# Sheet1.net
KiCad netlist of a schematic drawn in Altium Designer
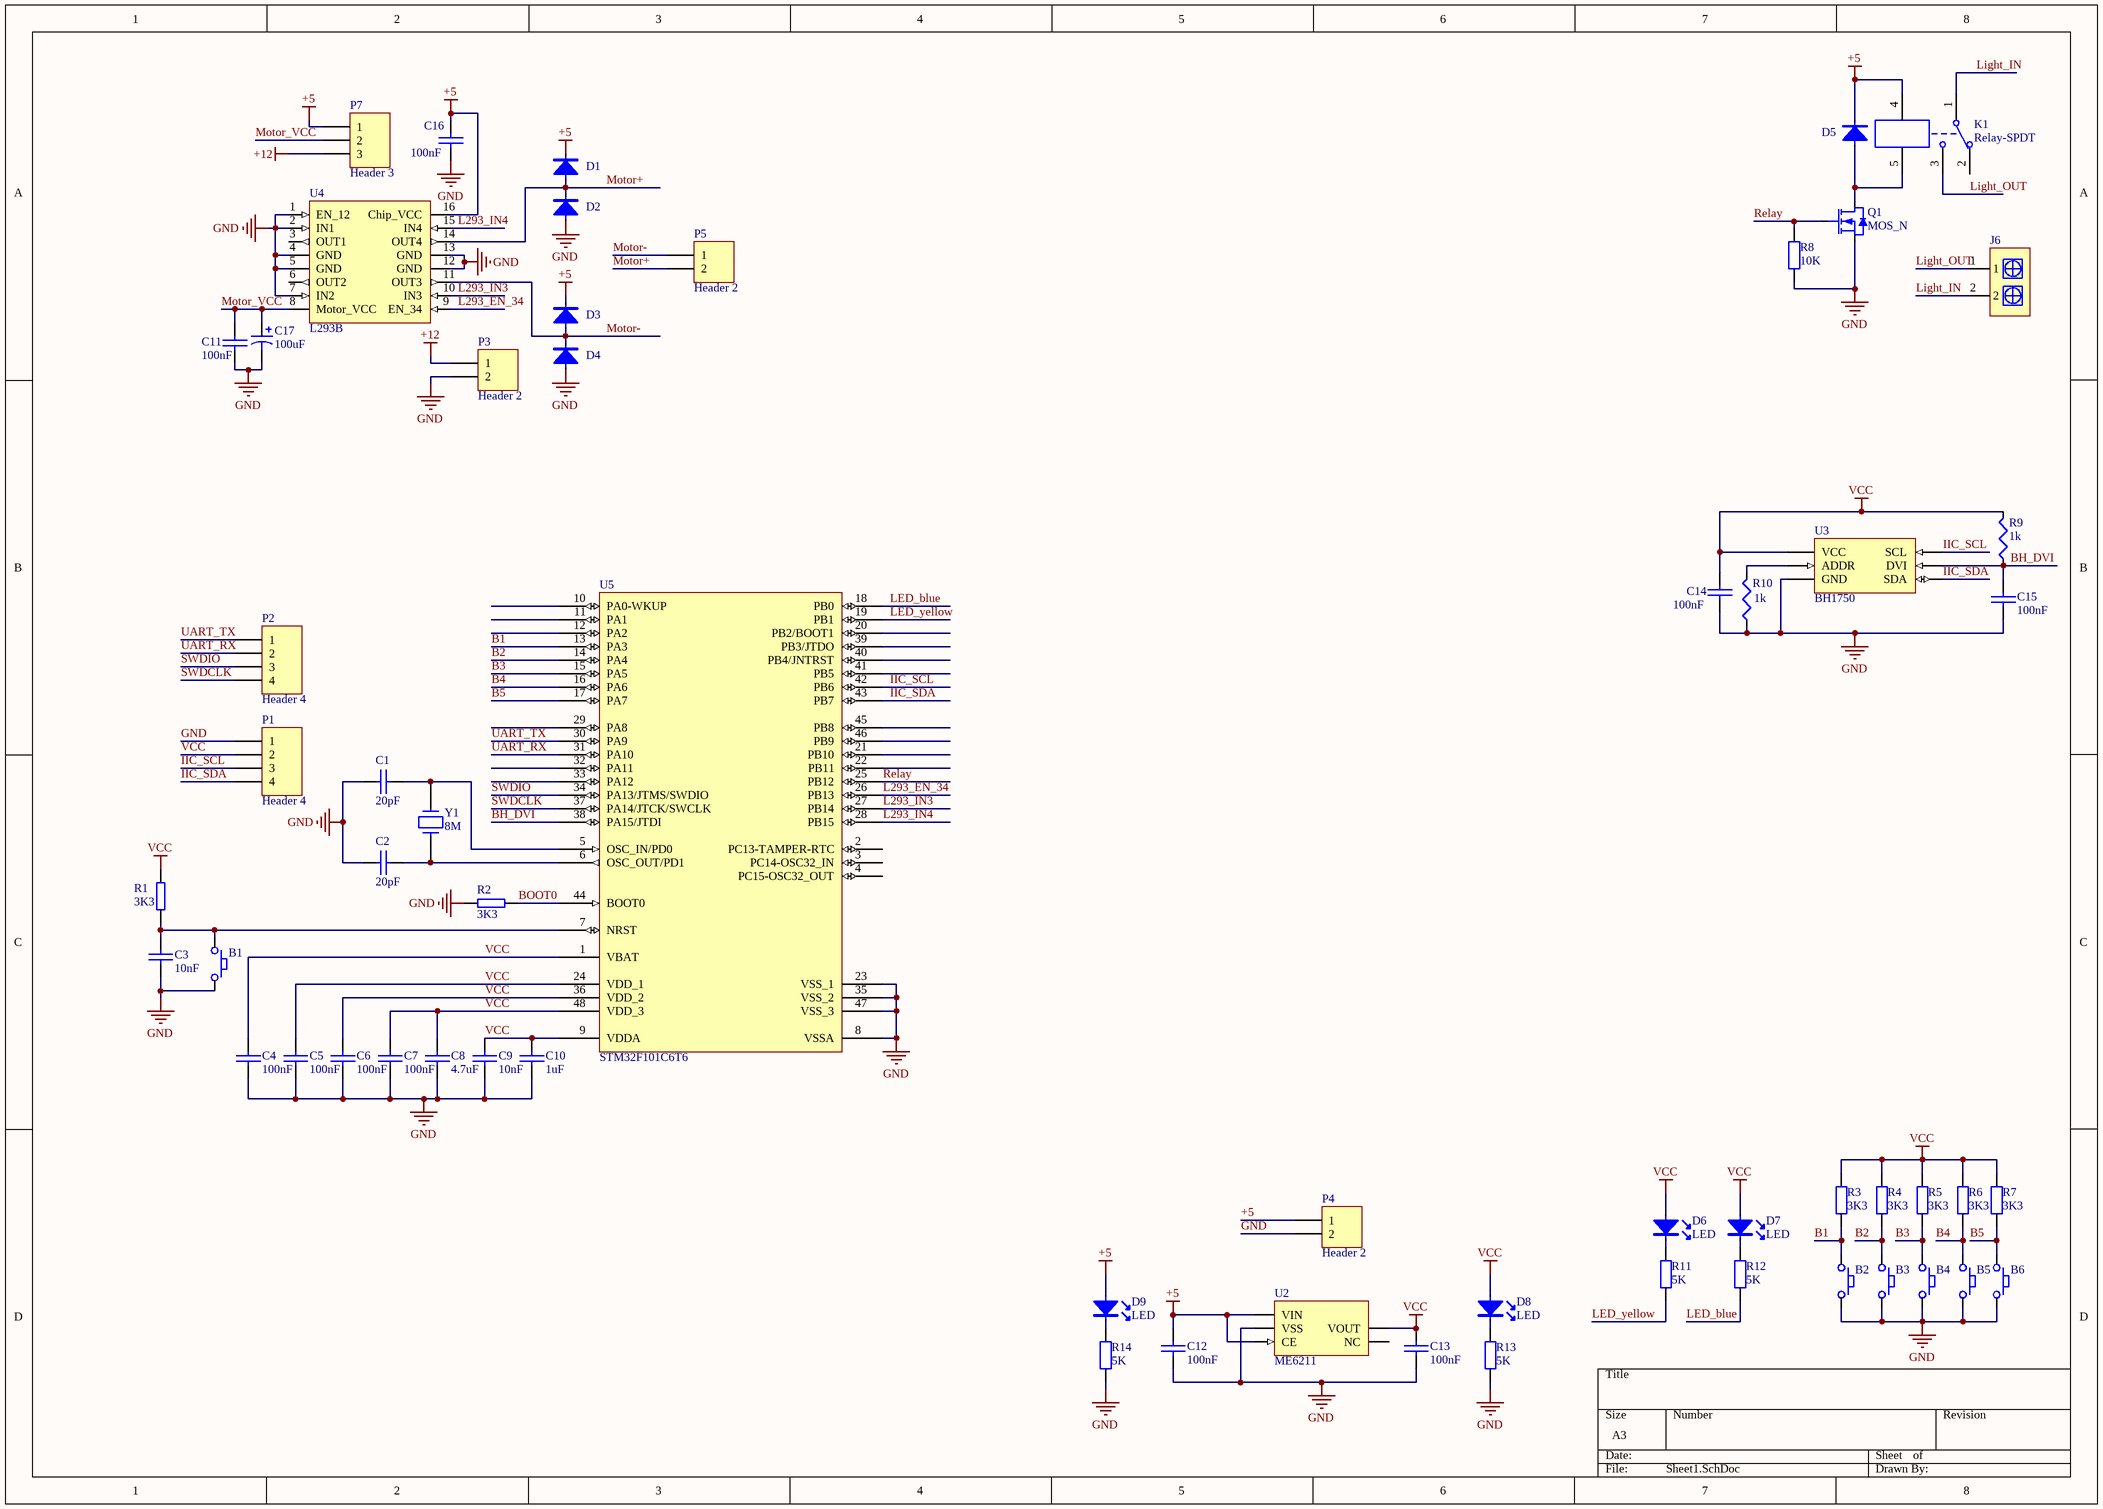
[diagram p0: Sheet1.SchDoc]

(export (version "E")
  (design (tool "Eeschema 10.0.6"))
  (components
    (comp (ref "B1") (value "button") (footprint "switch_2P") (libsource (lib "mylib") (part "button")))
    (comp (ref "B2") (value "button") (footprint "switch_2P") (libsource (lib "mylib") (part "button")))
    (comp (ref "B3") (value "button") (footprint "switch_2P") (libsource (lib "mylib") (part "button")))
    (comp (ref "B4") (value "button") (footprint "switch_2P") (libsource (lib "mylib") (part "button")))
    (comp (ref "B5") (value "button") (footprint "switch_2P") (libsource (lib "mylib") (part "button")))
    (comp (ref "B6") (value "button") (footprint "switch_2P") (libsource (lib "mylib") (part "button")))
    (comp (ref "C1")
      (value "20pF")
      (footprint "0603")
      (description "电容")
      (libsource (lib "SCH") (part "CAP"))
    )
    (comp (ref "C2")
      (value "20pF")
      (footprint "0603")
      (description "电容")
      (libsource (lib "SCH") (part "CAP"))
    )
    (comp (ref "C3")
      (value "10nF")
      (footprint "0603")
      (description "电容")
      (libsource (lib "SCH") (part "CAP"))
    )
    (comp (ref "C4")
      (value "100nF")
      (footprint "0603")
      (description "电容")
      (libsource (lib "SCH") (part "CAP"))
    )
    (comp (ref "C5")
      (value "100nF")
      (footprint "0603")
      (description "电容")
      (libsource (lib "SCH") (part "CAP"))
    )
    (comp (ref "C6")
      (value "100nF")
      (footprint "0603")
      (description "电容")
      (libsource (lib "SCH") (part "CAP"))
    )
    (comp (ref "C7")
      (value "100nF")
      (footprint "0603")
      (description "电容")
      (libsource (lib "SCH") (part "CAP"))
    )
    (comp (ref "C8")
      (value "4.7uF")
      (footprint "0603")
      (description "电容")
      (libsource (lib "SCH") (part "CAP"))
    )
    (comp (ref "C9")
      (value "10nF")
      (footprint "0603")
      (description "电容")
      (libsource (lib "SCH") (part "CAP"))
    )
    (comp (ref "C10")
      (value "1uF")
      (footprint "0603")
      (description "电容")
      (libsource (lib "SCH") (part "CAP"))
    )
    (comp (ref "C11")
      (value "100nF")
      (footprint "0603")
      (description "电容")
      (libsource (lib "SCH") (part "CAP"))
    )
    (comp (ref "C12")
      (value "100nF")
      (footprint "0603")
      (description "电容")
      (libsource (lib "SCH") (part "CAP"))
    )
    (comp (ref "C13")
      (value "100nF")
      (footprint "0603")
      (description "电容")
      (libsource (lib "SCH") (part "CAP"))
    )
    (comp (ref "C14")
      (value "100nF")
      (footprint "0603")
      (description "电容")
      (libsource (lib "SCH") (part "CAP"))
    )
    (comp (ref "C15")
      (value "100nF")
      (footprint "0603")
      (description "电容")
      (libsource (lib "SCH") (part "CAP"))
    )
    (comp (ref "C16")
      (value "100nF")
      (footprint "0603")
      (description "电容")
      (libsource (lib "SCH") (part "CAP"))
    )
    (comp (ref "C17")
      (value "100uF")
      (footprint "CAP_3.5_8mm")
      (description "Polarized Capacitor (Radial)")
      (fields (field (name "PUBLISHER") "Altium Limited"))
      (libsource (lib "Miscellaneous Devices") (part "Cap Pol1"))
    )
    (comp (ref "D1")
      (value "Diode_short")
      (footprint "SOD_123")
      (libsource (lib "mylib") (part "Diode_short"))
    )
    (comp (ref "D2")
      (value "Diode_short")
      (footprint "SOD_123")
      (libsource (lib "mylib") (part "Diode_short"))
    )
    (comp (ref "D3")
      (value "Diode_short")
      (footprint "SOD_123")
      (libsource (lib "mylib") (part "Diode_short"))
    )
    (comp (ref "D4")
      (value "Diode_short")
      (footprint "SOD_123")
      (libsource (lib "mylib") (part "Diode_short"))
    )
    (comp (ref "D5")
      (value "Diode_short")
      (footprint "SOD_123")
      (libsource (lib "mylib") (part "Diode_short"))
    )
    (comp (ref "D6") (value "LED") (footprint "0603-led") (libsource (lib "mylib") (part "LED")))
    (comp (ref "D7") (value "LED") (footprint "0603-led") (libsource (lib "mylib") (part "LED")))
    (comp (ref "D8") (value "LED") (footprint "0603-led") (libsource (lib "mylib") (part "LED")))
    (comp (ref "D9") (value "LED") (footprint "0603-led") (libsource (lib "mylib") (part "LED")))
    (comp (ref "J6")
      (value "7.62_螺丝固定端子")
      (footprint "7.62螺丝端子座")
      (libsource (lib "mylib") (part "7.62_螺丝固定端子"))
    )
    (comp (ref "K1")
      (value "Relay-SPDT")
      (footprint "relay_5pin")
      (description "Single-Pole Dual-Throw Relay")
      (fields (field (name "PUBLISHER") "Altium Limited"))
      (libsource (lib "Miscellaneous Devices") (part "Relay-SPDT"))
    )
    (comp (ref "P1")
      (value "Header 4")
      (footprint "HDR1X4")
      (description "Header, 4-Pin")
      (fields (field (name "PUBLISHER") "Altium Limited"))
      (libsource (lib "Miscellaneous Connectors") (part "Header 4"))
    )
    (comp (ref "P2")
      (value "Header 4")
      (footprint "HDR1X4")
      (description "Header, 4-Pin")
      (fields (field (name "PUBLISHER") "Altium Limited"))
      (libsource (lib "Miscellaneous Connectors") (part "Header 4"))
    )
    (comp (ref "P3")
      (value "Header 2")
      (footprint "HDR1X2")
      (description "Header, 2-Pin")
      (fields (field (name "PUBLISHER") "Altium Limited"))
      (libsource (lib "Miscellaneous Connectors") (part "Header 2"))
    )
    (comp (ref "P4")
      (value "Header 2")
      (footprint "HDR1X2")
      (description "Header, 2-Pin")
      (fields (field (name "PUBLISHER") "Altium Limited"))
      (libsource (lib "Miscellaneous Connectors") (part "Header 2"))
    )
    (comp (ref "P5")
      (value "Header 2")
      (footprint "2P_螺钉式接线端子_5.08mm")
      (description "Header, 2-Pin")
      (fields (field (name "PUBLISHER") "Altium Limited"))
      (libsource (lib "Miscellaneous Connectors") (part "Header 2"))
    )
    (comp (ref "P7")
      (value "Header 3")
      (footprint "HDR1X3")
      (description "Header, 3-Pin")
      (fields (field (name "PUBLISHER") "Altium Limited"))
      (libsource (lib "Miscellaneous Connectors") (part "Header 3"))
    )
    (comp (ref "Q1") (value "MOS_N") (footprint "zhang_PCB:SOT-23") (libsource (lib "mylib") (part "MOS_N")))
    (comp (ref "R1") (value "3K3") (footprint "0603") (libsource (lib "SCH") (part "RES2")))
    (comp (ref "R2") (value "3K3") (footprint "0603") (libsource (lib "SCH") (part "RES2")))
    (comp (ref "R3")
      (value "3K3")
      (footprint "0603")
      (description "Resistor")
      (fields (field (name "PUBLISHER") "Altium Limited"))
      (libsource (lib "Miscellaneous Devices") (part "Res2"))
    )
    (comp (ref "R4")
      (value "3K3")
      (footprint "0603")
      (description "Resistor")
      (fields (field (name "PUBLISHER") "Altium Limited"))
      (libsource (lib "Miscellaneous Devices") (part "Res2"))
    )
    (comp (ref "R5")
      (value "3K3")
      (footprint "0603")
      (description "Resistor")
      (fields (field (name "PUBLISHER") "Altium Limited"))
      (libsource (lib "Miscellaneous Devices") (part "Res2"))
    )
    (comp (ref "R6")
      (value "3K3")
      (footprint "0603")
      (description "Resistor")
      (fields (field (name "PUBLISHER") "Altium Limited"))
      (libsource (lib "Miscellaneous Devices") (part "Res2"))
    )
    (comp (ref "R7")
      (value "3K3")
      (footprint "0603")
      (description "Resistor")
      (fields (field (name "PUBLISHER") "Altium Limited"))
      (libsource (lib "Miscellaneous Devices") (part "Res2"))
    )
    (comp (ref "R8")
      (value "10K")
      (footprint "0603")
      (description "Resistor")
      (fields (field (name "PUBLISHER") "Altium Limited"))
      (libsource (lib "Miscellaneous Devices") (part "Res2"))
    )
    (comp (ref "R9") (value "1k") (footprint "0603") (libsource (lib "zhang_SCH") (part "RES1")))
    (comp (ref "R10") (value "1k") (footprint "0603") (libsource (lib "zhang_SCH") (part "RES1")))
    (comp (ref "R11")
      (value "5K")
      (footprint "0603")
      (description "Resistor")
      (fields (field (name "PUBLISHER") "Altium Limited"))
      (libsource (lib "Miscellaneous Devices") (part "Res2"))
    )
    (comp (ref "R12")
      (value "5K")
      (footprint "0603")
      (description "Resistor")
      (fields (field (name "PUBLISHER") "Altium Limited"))
      (libsource (lib "Miscellaneous Devices") (part "Res2"))
    )
    (comp (ref "R13")
      (value "5K")
      (footprint "0603")
      (description "Resistor")
      (fields (field (name "PUBLISHER") "Altium Limited"))
      (libsource (lib "Miscellaneous Devices") (part "Res2"))
    )
    (comp (ref "R14")
      (value "5K")
      (footprint "0603")
      (description "Resistor")
      (fields (field (name "PUBLISHER") "Altium Limited"))
      (libsource (lib "Miscellaneous Devices") (part "Res2"))
    )
    (comp (ref "U2") (value "ME6211") (footprint "SOT-23-5") (libsource (lib "mylib") (part "ME6211")))
    (comp (ref "U3") (value "BH1750") (footprint "BH1750") (libsource (lib "mylib") (part "BH1750")))
    (comp (ref "U4")
      (value "L293B")
      (footprint "DIP16")
      (description "4路电机驱动器")
      (libsource (lib "mylib") (part "L293B"))
    )
    (comp (ref "U5")
      (value "STM32F101C6T6")
      (footprint "LQFP48_M")
      (description "STM32 ARM-based 32-bit MCU with 32 Kbytes Flash, 48-pin LQFP, Industrial Temperature")
      (fields (field (name "PUBLISHER") "Altium Limited"))
      (libsource (lib "ST Microcontroller 32-Bit STM32") (part "STM32F101C6T6"))
    )
    (comp (ref "Y1")
      (value "8M")
      (footprint "mylib:5032")
      (description "晶体谐振器")
      (libsource (lib "SCH") (part "CRYSTAL"))
    )
  )
  (nets
    (net (code "1") (name "+5") (class "Default")
      (node (ref "C12") (pin "2") (pinfunction "2_2") (pintype "passive"))
      (node (ref "C16") (pin "2") (pinfunction "2_2") (pintype "passive"))
      (node (ref "D1") (pin "2") (pinfunction "2_2") (pintype "passive"))
      (node (ref "D3") (pin "2") (pinfunction "2_2") (pintype "passive"))
      (node (ref "D5") (pin "2") (pinfunction "2_2") (pintype "passive"))
      (node (ref "D9") (pin "1") (pinfunction "1_1") (pintype "passive"))
      (node (ref "K1") (pin "4") (pinfunction "4_4") (pintype "passive"))
      (node (ref "P4") (pin "1") (pinfunction "1_1") (pintype "passive"))
      (node (ref "P7") (pin "1") (pinfunction "1_1") (pintype "passive"))
      (node (ref "U2") (pin "1") (pinfunction "VIN_1") (pintype "power_in"))
      (node (ref "U2") (pin "3") (pinfunction "CE_3") (pintype "input"))
      (node (ref "U4") (pin "16") (pinfunction "Chip_VCC_16") (pintype "power_in"))
    )
    (net (code "2") (name "+12") (class "Default")
      (node (ref "P3") (pin "1") (pinfunction "1_1") (pintype "passive"))
      (node (ref "P7") (pin "3") (pinfunction "3_3") (pintype "passive"))
    )
    (net (code "3") (name "/B1") (class "Default")
      (node (ref "B2") (pin "1") (pinfunction "1_1") (pintype "passive"))
      (node (ref "R3") (pin "2") (pinfunction "2_2") (pintype "passive"))
      (node (ref "U5") (pin "13") (pinfunction "PA3_13") (pintype "bidirectional"))
    )
    (net (code "4") (name "/B2") (class "Default")
      (node (ref "B3") (pin "1") (pinfunction "1_1") (pintype "passive"))
      (node (ref "R4") (pin "2") (pinfunction "2_2") (pintype "passive"))
      (node (ref "U5") (pin "14") (pinfunction "PA4_14") (pintype "bidirectional"))
    )
    (net (code "5") (name "/B3") (class "Default")
      (node (ref "B4") (pin "1") (pinfunction "1_1") (pintype "passive"))
      (node (ref "R5") (pin "2") (pinfunction "2_2") (pintype "passive"))
      (node (ref "U5") (pin "15") (pinfunction "PA5_15") (pintype "bidirectional"))
    )
    (net (code "6") (name "/B4") (class "Default")
      (node (ref "B5") (pin "1") (pinfunction "1_1") (pintype "passive"))
      (node (ref "R6") (pin "2") (pinfunction "2_2") (pintype "passive"))
      (node (ref "U5") (pin "16") (pinfunction "PA6_16") (pintype "bidirectional"))
    )
    (net (code "7") (name "/B5") (class "Default")
      (node (ref "B6") (pin "1") (pinfunction "1_1") (pintype "passive"))
      (node (ref "R7") (pin "2") (pinfunction "2_2") (pintype "passive"))
      (node (ref "U5") (pin "17") (pinfunction "PA7_17") (pintype "bidirectional"))
    )
    (net (code "8") (name "/BH_DVI") (class "Default")
      (node (ref "C15") (pin "2") (pinfunction "2_2") (pintype "passive"))
      (node (ref "R9") (pin "1") (pinfunction "1_1") (pintype "passive"))
      (node (ref "U3") (pin "5") (pinfunction "DVI_5") (pintype "input"))
      (node (ref "U5") (pin "38") (pinfunction "PA15/JTDI_38") (pintype "bidirectional"))
    )
    (net (code "9") (name "/BOOT0") (class "Default")
      (node (ref "R2") (pin "2") (pinfunction "2_2") (pintype "passive"))
      (node (ref "U5") (pin "44") (pinfunction "BOOT0_44") (pintype "input"))
    )
    (net (code "10") (name "/IIC_SCL") (class "Default")
      (node (ref "P1") (pin "3") (pinfunction "3_3") (pintype "passive"))
      (node (ref "U3") (pin "6") (pinfunction "SCL_6") (pintype "input"))
      (node (ref "U5") (pin "42") (pinfunction "PB6_42") (pintype "bidirectional"))
    )
    (net (code "11") (name "/IIC_SDA") (class "Default")
      (node (ref "P1") (pin "4") (pinfunction "4_4") (pintype "passive"))
      (node (ref "U3") (pin "4") (pinfunction "SDA_4") (pintype "bidirectional"))
      (node (ref "U5") (pin "43") (pinfunction "PB7_43") (pintype "bidirectional"))
    )
    (net (code "12") (name "/L293_EN_34") (class "Default")
      (node (ref "U4") (pin "9") (pinfunction "EN_34_9") (pintype "input"))
      (node (ref "U5") (pin "26") (pinfunction "PB13_26") (pintype "bidirectional"))
    )
    (net (code "13") (name "/L293_IN3") (class "Default")
      (node (ref "U4") (pin "10") (pinfunction "IN3_10") (pintype "input"))
      (node (ref "U5") (pin "27") (pinfunction "PB14_27") (pintype "bidirectional"))
    )
    (net (code "14") (name "/L293_IN4") (class "Default")
      (node (ref "U4") (pin "15") (pinfunction "IN4_15") (pintype "input"))
      (node (ref "U5") (pin "28") (pinfunction "PB15_28") (pintype "bidirectional"))
    )
    (net (code "15") (name "/LED_blue") (class "Default")
      (node (ref "R12") (pin "2") (pinfunction "2_2") (pintype "passive"))
      (node (ref "U5") (pin "18") (pinfunction "PB0_18") (pintype "bidirectional"))
    )
    (net (code "16") (name "/LED_yellow") (class "Default")
      (node (ref "R11") (pin "2") (pinfunction "2_2") (pintype "passive"))
      (node (ref "U5") (pin "19") (pinfunction "PB1_19") (pintype "bidirectional"))
    )
    (net (code "17") (name "/Light_IN") (class "Default")
      (node (ref "J6") (pin "2") (pinfunction "2_2") (pintype "passive"))
      (node (ref "K1") (pin "1") (pinfunction "1_1") (pintype "passive"))
    )
    (net (code "18") (name "/Light_OUT") (class "Default")
      (node (ref "J6") (pin "1") (pinfunction "1_1") (pintype "passive"))
      (node (ref "K1") (pin "3") (pinfunction "3_3") (pintype "passive"))
    )
    (net (code "19") (name "/Motor+") (class "Default")
      (node (ref "D1") (pin "1") (pinfunction "1_1") (pintype "passive"))
      (node (ref "D2") (pin "2") (pinfunction "2_2") (pintype "passive"))
      (node (ref "P5") (pin "2") (pinfunction "2_2") (pintype "passive"))
      (node (ref "U4") (pin "14") (pinfunction "OUT4_14") (pintype "output"))
    )
    (net (code "20") (name "/Motor-") (class "Default")
      (node (ref "D3") (pin "1") (pinfunction "1_1") (pintype "passive"))
      (node (ref "D4") (pin "2") (pinfunction "2_2") (pintype "passive"))
      (node (ref "P5") (pin "1") (pinfunction "1_1") (pintype "passive"))
      (node (ref "U4") (pin "11") (pinfunction "OUT3_11") (pintype "output"))
    )
    (net (code "21") (name "/Motor_VCC") (class "Default")
      (node (ref "C11") (pin "2") (pinfunction "2_2") (pintype "passive"))
      (node (ref "C17") (pin "1") (pinfunction "1_1") (pintype "passive"))
      (node (ref "P7") (pin "2") (pinfunction "2_2") (pintype "passive"))
      (node (ref "U4") (pin "8") (pinfunction "Motor_VCC_8") (pintype "power_in"))
    )
    (net (code "22") (name "/Relay") (class "Default")
      (node (ref "Q1") (pin "1") (pinfunction "G_1") (pintype "passive"))
      (node (ref "R8") (pin "1") (pinfunction "1_1") (pintype "passive"))
      (node (ref "U5") (pin "25") (pinfunction "PB12_25") (pintype "bidirectional"))
    )
    (net (code "23") (name "/SWDCLK") (class "Default")
      (node (ref "P2") (pin "4") (pinfunction "4_4") (pintype "passive"))
      (node (ref "U5") (pin "37") (pinfunction "PA14/JTCK/SWCLK_37") (pintype "bidirectional"))
    )
    (net (code "24") (name "/SWDIO") (class "Default")
      (node (ref "P2") (pin "3") (pinfunction "3_3") (pintype "passive"))
      (node (ref "U5") (pin "34") (pinfunction "PA13/JTMS/SWDIO_34") (pintype "bidirectional"))
    )
    (net (code "25") (name "/UART_RX") (class "Default")
      (node (ref "P2") (pin "2") (pinfunction "2_2") (pintype "passive"))
      (node (ref "U5") (pin "31") (pinfunction "PA10_31") (pintype "bidirectional"))
    )
    (net (code "26") (name "/UART_TX") (class "Default")
      (node (ref "P2") (pin "1") (pinfunction "1_1") (pintype "passive"))
      (node (ref "U5") (pin "30") (pinfunction "PA9_30") (pintype "bidirectional"))
    )
    (net (code "27") (name "GND") (class "Default")
      (node (ref "B1") (pin "2") (pinfunction "2_2") (pintype "passive"))
      (node (ref "B2") (pin "2") (pinfunction "2_2") (pintype "passive"))
      (node (ref "B3") (pin "2") (pinfunction "2_2") (pintype "passive"))
      (node (ref "B4") (pin "2") (pinfunction "2_2") (pintype "passive"))
      (node (ref "B5") (pin "2") (pinfunction "2_2") (pintype "passive"))
      (node (ref "B6") (pin "2") (pinfunction "2_2") (pintype "passive"))
      (node (ref "C1") (pin "1") (pinfunction "1_1") (pintype "passive"))
      (node (ref "C10") (pin "1") (pinfunction "1_1") (pintype "passive"))
      (node (ref "C11") (pin "1") (pinfunction "1_1") (pintype "passive"))
      (node (ref "C12") (pin "1") (pinfunction "1_1") (pintype "passive"))
      (node (ref "C13") (pin "1") (pinfunction "1_1") (pintype "passive"))
      (node (ref "C14") (pin "1") (pinfunction "1_1") (pintype "passive"))
      (node (ref "C15") (pin "1") (pinfunction "1_1") (pintype "passive"))
      (node (ref "C16") (pin "1") (pinfunction "1_1") (pintype "passive"))
      (node (ref "C17") (pin "2") (pinfunction "2_2") (pintype "passive"))
      (node (ref "C2") (pin "1") (pinfunction "1_1") (pintype "passive"))
      (node (ref "C3") (pin "1") (pinfunction "1_1") (pintype "passive"))
      (node (ref "C4") (pin "1") (pinfunction "1_1") (pintype "passive"))
      (node (ref "C5") (pin "1") (pinfunction "1_1") (pintype "passive"))
      (node (ref "C6") (pin "1") (pinfunction "1_1") (pintype "passive"))
      (node (ref "C7") (pin "1") (pinfunction "1_1") (pintype "passive"))
      (node (ref "C8") (pin "1") (pinfunction "1_1") (pintype "passive"))
      (node (ref "C9") (pin "1") (pinfunction "1_1") (pintype "passive"))
      (node (ref "D2") (pin "1") (pinfunction "1_1") (pintype "passive"))
      (node (ref "D4") (pin "1") (pinfunction "1_1") (pintype "passive"))
      (node (ref "P1") (pin "1") (pinfunction "1_1") (pintype "passive"))
      (node (ref "P3") (pin "2") (pinfunction "2_2") (pintype "passive"))
      (node (ref "P4") (pin "2") (pinfunction "2_2") (pintype "passive"))
      (node (ref "Q1") (pin "2") (pinfunction "S_2") (pintype "passive"))
      (node (ref "R10") (pin "1") (pinfunction "1_1") (pintype "passive"))
      (node (ref "R13") (pin "2") (pinfunction "2_2") (pintype "passive"))
      (node (ref "R14") (pin "2") (pinfunction "2_2") (pintype "passive"))
      (node (ref "R2") (pin "1") (pinfunction "1_1") (pintype "passive"))
      (node (ref "R8") (pin "2") (pinfunction "2_2") (pintype "passive"))
      (node (ref "U2") (pin "2") (pinfunction "VSS_2") (pintype "power_in"))
      (node (ref "U3") (pin "3") (pinfunction "GND_3") (pintype "power_in"))
      (node (ref "U4") (pin "1") (pinfunction "EN_12_1") (pintype "input"))
      (node (ref "U4") (pin "12") (pinfunction "GND_12") (pintype "power_in"))
      (node (ref "U4") (pin "13") (pinfunction "GND_13") (pintype "power_in"))
      (node (ref "U4") (pin "2") (pinfunction "IN1_2") (pintype "input"))
      (node (ref "U4") (pin "4") (pinfunction "GND_4") (pintype "power_in"))
      (node (ref "U4") (pin "5") (pinfunction "GND_5") (pintype "power_in"))
      (node (ref "U4") (pin "7") (pinfunction "IN2_7") (pintype "input"))
      (node (ref "U5") (pin "23") (pinfunction "VSS_1_23") (pintype "power_in"))
      (node (ref "U5") (pin "35") (pinfunction "VSS_2_35") (pintype "power_in"))
      (node (ref "U5") (pin "47") (pinfunction "VSS_3_47") (pintype "power_in"))
      (node (ref "U5") (pin "8") (pinfunction "VSSA_8") (pintype "power_in"))
    )
    (net (code "28") (name "Net-(D6-Pad2)") (class "Default")
      (node (ref "D6") (pin "2") (pinfunction "2_2") (pintype "passive"))
      (node (ref "R11") (pin "1") (pinfunction "1_1") (pintype "passive"))
    )
    (net (code "29") (name "Net-(D7-Pad2)") (class "Default")
      (node (ref "D7") (pin "2") (pinfunction "2_2") (pintype "passive"))
      (node (ref "R12") (pin "1") (pinfunction "1_1") (pintype "passive"))
    )
    (net (code "30") (name "Net-(D8-Pad2)") (class "Default")
      (node (ref "D8") (pin "2") (pinfunction "2_2") (pintype "passive"))
      (node (ref "R13") (pin "1") (pinfunction "1_1") (pintype "passive"))
    )
    (net (code "31") (name "Net-(D9-Pad2)") (class "Default")
      (node (ref "D9") (pin "2") (pinfunction "2_2") (pintype "passive"))
      (node (ref "R14") (pin "1") (pinfunction "1_1") (pintype "passive"))
    )
    (net (code "32") (name "Net-(Q1-D)") (class "Default")
      (node (ref "D5") (pin "1") (pinfunction "1_1") (pintype "passive"))
      (node (ref "K1") (pin "5") (pinfunction "5_5") (pintype "passive"))
      (node (ref "Q1") (pin "3") (pinfunction "D_3") (pintype "passive"))
    )
    (net (code "33") (name "Net-(U3-ADDR)") (class "Default")
      (node (ref "R10") (pin "2") (pinfunction "2_2") (pintype "passive"))
      (node (ref "U3") (pin "2") (pinfunction "ADDR_2") (pintype "input"))
    )
    (net (code "34") (name "Net-(U5-NRST)") (class "Default")
      (node (ref "B1") (pin "1") (pinfunction "1_1") (pintype "passive"))
      (node (ref "C3") (pin "2") (pinfunction "2_2") (pintype "passive"))
      (node (ref "R1") (pin "1") (pinfunction "1_1") (pintype "passive"))
      (node (ref "U5") (pin "7") (pinfunction "NRST_7") (pintype "bidirectional"))
    )
    (net (code "35") (name "Net-(U5-OSC_IN{slash}PD0)") (class "Default")
      (node (ref "C1") (pin "2") (pinfunction "2_2") (pintype "passive"))
      (node (ref "U5") (pin "5") (pinfunction "OSC_IN/PD0_5") (pintype "input"))
      (node (ref "Y1") (pin "2") (pinfunction "2_2") (pintype "passive"))
    )
    (net (code "36") (name "Net-(U5-OSC_OUT{slash}PD1)") (class "Default")
      (node (ref "C2") (pin "2") (pinfunction "2_2") (pintype "passive"))
      (node (ref "U5") (pin "6") (pinfunction "OSC_OUT/PD1_6") (pintype "output"))
      (node (ref "Y1") (pin "1") (pinfunction "1_1") (pintype "passive"))
    )
    (net (code "37") (name "VCC") (class "Default")
      (node (ref "C10") (pin "2") (pinfunction "2_2") (pintype "passive"))
      (node (ref "C13") (pin "2") (pinfunction "2_2") (pintype "passive"))
      (node (ref "C14") (pin "2") (pinfunction "2_2") (pintype "passive"))
      (node (ref "C4") (pin "2") (pinfunction "2_2") (pintype "passive"))
      (node (ref "C5") (pin "2") (pinfunction "2_2") (pintype "passive"))
      (node (ref "C6") (pin "2") (pinfunction "2_2") (pintype "passive"))
      (node (ref "C7") (pin "2") (pinfunction "2_2") (pintype "passive"))
      (node (ref "C8") (pin "2") (pinfunction "2_2") (pintype "passive"))
      (node (ref "C9") (pin "2") (pinfunction "2_2") (pintype "passive"))
      (node (ref "D6") (pin "1") (pinfunction "1_1") (pintype "passive"))
      (node (ref "D7") (pin "1") (pinfunction "1_1") (pintype "passive"))
      (node (ref "D8") (pin "1") (pinfunction "1_1") (pintype "passive"))
      (node (ref "P1") (pin "2") (pinfunction "2_2") (pintype "passive"))
      (node (ref "R1") (pin "2") (pinfunction "2_2") (pintype "passive"))
      (node (ref "R3") (pin "1") (pinfunction "1_1") (pintype "passive"))
      (node (ref "R4") (pin "1") (pinfunction "1_1") (pintype "passive"))
      (node (ref "R5") (pin "1") (pinfunction "1_1") (pintype "passive"))
      (node (ref "R6") (pin "1") (pinfunction "1_1") (pintype "passive"))
      (node (ref "R7") (pin "1") (pinfunction "1_1") (pintype "passive"))
      (node (ref "R9") (pin "2") (pinfunction "2_2") (pintype "passive"))
      (node (ref "U2") (pin "5") (pinfunction "VOUT_5") (pintype "power_in"))
      (node (ref "U3") (pin "1") (pinfunction "VCC_1") (pintype "power_in"))
      (node (ref "U5") (pin "1") (pinfunction "VBAT_1") (pintype "power_in"))
      (node (ref "U5") (pin "24") (pinfunction "VDD_1_24") (pintype "power_in"))
      (node (ref "U5") (pin "36") (pinfunction "VDD_2_36") (pintype "power_in"))
      (node (ref "U5") (pin "48") (pinfunction "VDD_3_48") (pintype "power_in"))
      (node (ref "U5") (pin "9") (pinfunction "VDDA_9") (pintype "power_in"))
    )
    (net (code "38") (name "unconnected-(K1-Pad2)") (class "Default")
      (node (ref "K1") (pin "2") (pinfunction "2_2") (pintype "passive"))
    )
    (net (code "39") (name "unconnected-(U2-NC-Pad4)") (class "Default")
      (node (ref "U2") (pin "4") (pinfunction "NC_4") (pintype "passive"))
    )
    (net (code "40") (name "unconnected-(U4-OUT1-Pad3)") (class "Default")
      (node (ref "U4") (pin "3") (pinfunction "OUT1_3") (pintype "output"))
    )
    (net (code "41") (name "unconnected-(U4-OUT2-Pad6)") (class "Default")
      (node (ref "U4") (pin "6") (pinfunction "OUT2_6") (pintype "output"))
    )
    (net (code "42") (name "unconnected-(U5-PA0-WKUP-Pad10)") (class "Default")
      (node (ref "U5") (pin "10") (pinfunction "PA0-WKUP_10") (pintype "bidirectional"))
    )
    (net (code "43") (name "unconnected-(U5-PA1-Pad11)") (class "Default")
      (node (ref "U5") (pin "11") (pinfunction "PA1_11") (pintype "bidirectional"))
    )
    (net (code "44") (name "unconnected-(U5-PA2-Pad12)") (class "Default")
      (node (ref "U5") (pin "12") (pinfunction "PA2_12") (pintype "bidirectional"))
    )
    (net (code "45") (name "unconnected-(U5-PA8-Pad29)") (class "Default")
      (node (ref "U5") (pin "29") (pinfunction "PA8_29") (pintype "bidirectional"))
    )
    (net (code "46") (name "unconnected-(U5-PA11-Pad32)") (class "Default")
      (node (ref "U5") (pin "32") (pinfunction "PA11_32") (pintype "bidirectional"))
    )
    (net (code "47") (name "unconnected-(U5-PA12-Pad33)") (class "Default")
      (node (ref "U5") (pin "33") (pinfunction "PA12_33") (pintype "bidirectional"))
    )
    (net (code "48") (name "unconnected-(U5-PB2{slash}BOOT1-Pad20)") (class "Default")
      (node (ref "U5") (pin "20") (pinfunction "PB2/BOOT1_20") (pintype "bidirectional"))
    )
    (net (code "49") (name "unconnected-(U5-PB3{slash}JTDO-Pad39)") (class "Default")
      (node (ref "U5") (pin "39") (pinfunction "PB3/JTDO_39") (pintype "bidirectional"))
    )
    (net (code "50") (name "unconnected-(U5-PB4{slash}JNTRST-Pad40)") (class "Default")
      (node (ref "U5") (pin "40") (pinfunction "PB4/JNTRST_40") (pintype "bidirectional"))
    )
    (net (code "51") (name "unconnected-(U5-PB5-Pad41)") (class "Default")
      (node (ref "U5") (pin "41") (pinfunction "PB5_41") (pintype "bidirectional"))
    )
    (net (code "52") (name "unconnected-(U5-PB8-Pad45)") (class "Default")
      (node (ref "U5") (pin "45") (pinfunction "PB8_45") (pintype "bidirectional"))
    )
    (net (code "53") (name "unconnected-(U5-PB9-Pad46)") (class "Default")
      (node (ref "U5") (pin "46") (pinfunction "PB9_46") (pintype "bidirectional"))
    )
    (net (code "54") (name "unconnected-(U5-PB10-Pad21)") (class "Default")
      (node (ref "U5") (pin "21") (pinfunction "PB10_21") (pintype "bidirectional"))
    )
    (net (code "55") (name "unconnected-(U5-PB11-Pad22)") (class "Default")
      (node (ref "U5") (pin "22") (pinfunction "PB11_22") (pintype "bidirectional"))
    )
    (net (code "56") (name "unconnected-(U5-PC13-TAMPER-RTC-Pad2)") (class "Default")
      (node (ref "U5") (pin "2") (pinfunction "PC13-TAMPER-RTC_2") (pintype "bidirectional"))
    )
    (net (code "57") (name "unconnected-(U5-PC14-OSC32_IN-Pad3)") (class "Default")
      (node (ref "U5") (pin "3") (pinfunction "PC14-OSC32_IN_3") (pintype "bidirectional"))
    )
    (net (code "58") (name "unconnected-(U5-PC15-OSC32_OUT-Pad4)") (class "Default")
      (node (ref "U5") (pin "4") (pinfunction "PC15-OSC32_OUT_4") (pintype "bidirectional"))
    )
  )
)
